# DualEncoderBoard-v1_0.net
KiCad netlist of a schematic drawn in EAGLE
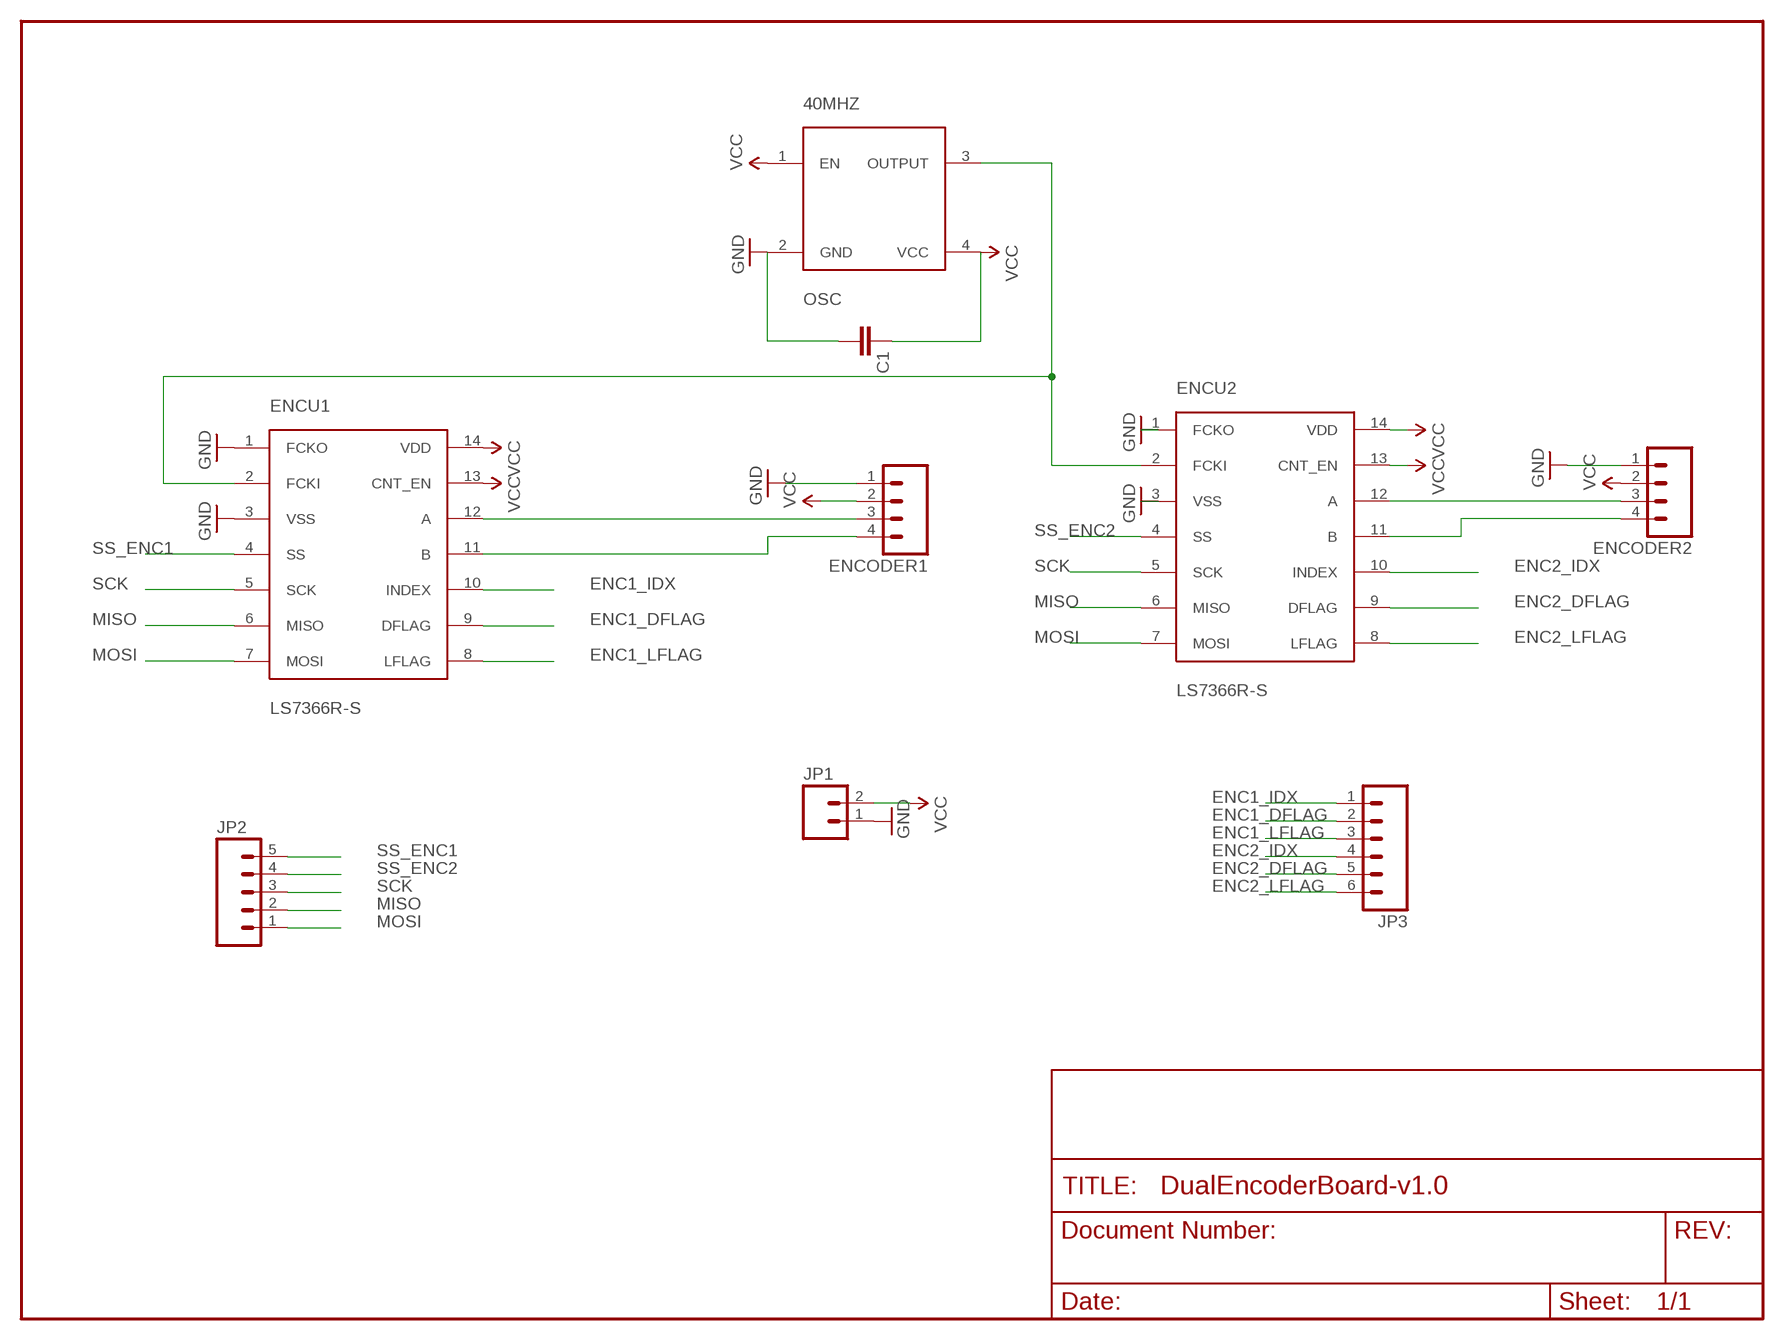
[diagram p0: schematic, sheet 1]

(export (version "E")
  (design (tool "Eeschema 10.0.6"))
  (components
    (comp (ref "40MHZ")
      (value "OSC")
      (footprint "eagle-import:CB3OSCILLATOR")
      (libsource (lib "eagle-import") (part "OSC"))
    )
    (comp (ref "C1")
      (value "CAPKIT")
      (footprint "eagle-import:CAP-PTH-SMALL-KIT")
      (libsource (lib "eagle-import") (part "CAPKIT"))
    )
    (comp (ref "ENCODER1")
      (value "M04POLAR")
      (footprint "eagle-import:MOLEX-1X4")
      (libsource (lib "eagle-import") (part "M04POLAR"))
    )
    (comp (ref "ENCODER2")
      (value "M04POLAR")
      (footprint "eagle-import:MOLEX-1X4")
      (libsource (lib "eagle-import") (part "M04POLAR"))
    )
    (comp (ref "ENCU1")
      (value "LS7366R-S")
      (footprint "eagle-import:SO14")
      (libsource (lib "eagle-import") (part "LS7366R-S"))
    )
    (comp (ref "ENCU2")
      (value "LS7366R-S")
      (footprint "eagle-import:SO14")
      (libsource (lib "eagle-import") (part "LS7366R-S"))
    )
    (comp (ref "JP1")
      (value "M02-JST-2MM-SMT")
      (footprint "eagle-import:JST-2-SMD")
      (libsource (lib "eagle-import") (part "M02-JST-2MM-SMT"))
    )
    (comp (ref "JP2")
      (value "M05PTH")
      (footprint "eagle-import:1X05")
      (libsource (lib "eagle-import") (part "M05PTH"))
    )
    (comp (ref "JP3")
      (value "M06SIP")
      (footprint "eagle-import:1X06")
      (libsource (lib "eagle-import") (part "M06SIP"))
    )
  )
  (nets
    (net (code "1") (name "/ENC1_DFLAG") (class "Default")
      (node (ref "ENCU1") (pin "9") (pinfunction "DFLAG_9") (pintype "output"))
      (node (ref "JP3") (pin "2") (pinfunction "2_2") (pintype "passive"))
    )
    (net (code "2") (name "/ENC1_IDX") (class "Default")
      (node (ref "ENCU1") (pin "10") (pinfunction "INDEX_10") (pintype "input"))
      (node (ref "JP3") (pin "1") (pinfunction "1_1") (pintype "passive"))
    )
    (net (code "3") (name "/ENC1_LFLAG") (class "Default")
      (node (ref "ENCU1") (pin "8") (pinfunction "LFLAG_8") (pintype "output"))
      (node (ref "JP3") (pin "3") (pinfunction "3_3") (pintype "passive"))
    )
    (net (code "4") (name "/ENC2_DFLAG") (class "Default")
      (node (ref "ENCU2") (pin "9") (pinfunction "DFLAG_9") (pintype "output"))
      (node (ref "JP3") (pin "5") (pinfunction "5_5") (pintype "passive"))
    )
    (net (code "5") (name "/ENC2_IDX") (class "Default")
      (node (ref "ENCU2") (pin "10") (pinfunction "INDEX_10") (pintype "input"))
      (node (ref "JP3") (pin "4") (pinfunction "4_4") (pintype "passive"))
    )
    (net (code "6") (name "/ENC2_LFLAG") (class "Default")
      (node (ref "ENCU2") (pin "8") (pinfunction "LFLAG_8") (pintype "output"))
      (node (ref "JP3") (pin "6") (pinfunction "6_6") (pintype "passive"))
    )
    (net (code "7") (name "/MISO") (class "Default")
      (node (ref "ENCU1") (pin "6") (pinfunction "MISO_6") (pintype "output"))
      (node (ref "ENCU2") (pin "6") (pinfunction "MISO_6") (pintype "output"))
      (node (ref "JP2") (pin "2") (pinfunction "2_2") (pintype "passive"))
    )
    (net (code "8") (name "/MOSI") (class "Default")
      (node (ref "ENCU1") (pin "7") (pinfunction "MOSI_7") (pintype "input"))
      (node (ref "ENCU2") (pin "7") (pinfunction "MOSI_7") (pintype "input"))
      (node (ref "JP2") (pin "1") (pinfunction "1_1") (pintype "passive"))
    )
    (net (code "9") (name "/SCK") (class "Default")
      (node (ref "ENCU1") (pin "5") (pinfunction "SCK_5") (pintype "input"))
      (node (ref "ENCU2") (pin "5") (pinfunction "SCK_5") (pintype "input"))
      (node (ref "JP2") (pin "3") (pinfunction "3_3") (pintype "passive"))
    )
    (net (code "10") (name "/SS_ENC1") (class "Default")
      (node (ref "ENCU1") (pin "4") (pinfunction "SS_4") (pintype "input"))
      (node (ref "JP2") (pin "5") (pinfunction "5_5") (pintype "passive"))
    )
    (net (code "11") (name "/SS_ENC2") (class "Default")
      (node (ref "ENCU2") (pin "4") (pinfunction "SS_4") (pintype "input"))
      (node (ref "JP2") (pin "4") (pinfunction "4_4") (pintype "passive"))
    )
    (net (code "12") (name "GND") (class "Default")
      (node (ref "40MHZ") (pin "2") (pinfunction "GND_2") (pintype "input"))
      (node (ref "C1") (pin "2") (pinfunction "2_2") (pintype "passive"))
      (node (ref "ENCODER1") (pin "1") (pinfunction "1_1") (pintype "passive"))
      (node (ref "ENCODER2") (pin "1") (pinfunction "1_1") (pintype "passive"))
      (node (ref "ENCU1") (pin "1") (pinfunction "FCKO_1") (pintype "output"))
      (node (ref "ENCU1") (pin "3") (pinfunction "VSS_3") (pintype "power_in"))
      (node (ref "ENCU2") (pin "1") (pinfunction "FCKO_1") (pintype "output"))
      (node (ref "ENCU2") (pin "3") (pinfunction "VSS_3") (pintype "power_in"))
      (node (ref "JP1") (pin "1") (pinfunction "1_1") (pintype "passive"))
    )
    (net (code "13") (name "Net-(40MHZ-OUTPUT)") (class "Default")
      (node (ref "40MHZ") (pin "3") (pinfunction "OUTPUT_3") (pintype "output"))
      (node (ref "ENCU1") (pin "2") (pinfunction "FCKI_2") (pintype "input"))
      (node (ref "ENCU2") (pin "2") (pinfunction "FCKI_2") (pintype "input"))
    )
    (net (code "14") (name "Net-(ENCU1-A)") (class "Default")
      (node (ref "ENCODER1") (pin "3") (pinfunction "3_3") (pintype "passive"))
      (node (ref "ENCU1") (pin "12") (pinfunction "A_12") (pintype "input"))
    )
    (net (code "15") (name "Net-(ENCU1-B)") (class "Default")
      (node (ref "ENCODER1") (pin "4") (pinfunction "4_4") (pintype "passive"))
      (node (ref "ENCU1") (pin "11") (pinfunction "B_11") (pintype "input"))
    )
    (net (code "16") (name "Net-(ENCU2-A)") (class "Default")
      (node (ref "ENCODER2") (pin "3") (pinfunction "3_3") (pintype "passive"))
      (node (ref "ENCU2") (pin "12") (pinfunction "A_12") (pintype "input"))
    )
    (net (code "17") (name "Net-(ENCU2-B)") (class "Default")
      (node (ref "ENCODER2") (pin "4") (pinfunction "4_4") (pintype "passive"))
      (node (ref "ENCU2") (pin "11") (pinfunction "B_11") (pintype "input"))
    )
    (net (code "18") (name "VCC") (class "Default")
      (node (ref "40MHZ") (pin "1") (pinfunction "EN_1") (pintype "input"))
      (node (ref "40MHZ") (pin "4") (pinfunction "VCC_4") (pintype "input"))
      (node (ref "C1") (pin "1") (pinfunction "1_1") (pintype "passive"))
      (node (ref "ENCODER1") (pin "2") (pinfunction "2_2") (pintype "passive"))
      (node (ref "ENCODER2") (pin "2") (pinfunction "2_2") (pintype "passive"))
      (node (ref "ENCU1") (pin "13") (pinfunction "CNT_EN_13") (pintype "input"))
      (node (ref "ENCU1") (pin "14") (pinfunction "VDD_14") (pintype "power_in"))
      (node (ref "ENCU2") (pin "13") (pinfunction "CNT_EN_13") (pintype "input"))
      (node (ref "ENCU2") (pin "14") (pinfunction "VDD_14") (pintype "power_in"))
      (node (ref "JP1") (pin "2") (pinfunction "2_2") (pintype "passive"))
    )
  )
)
